# new_board_p_dan_n.net
KiCad netlist of a schematic drawn in EAGLE
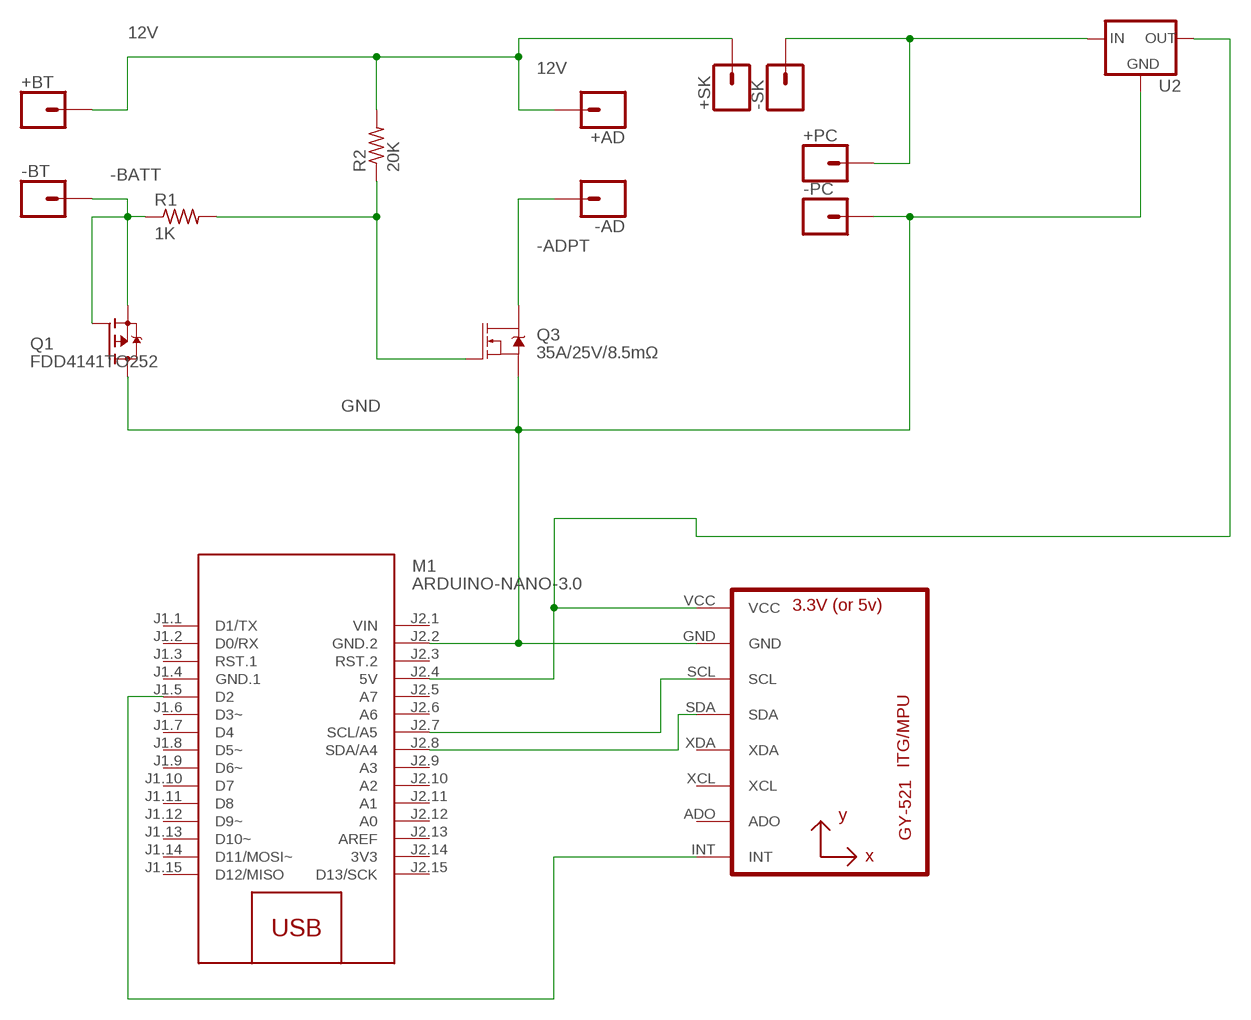
[diagram p0: schematic, sheet 1]

(export (version "E")
  (design (tool "Eeschema 10.0.6"))
  (components
    (comp (ref "+AD")
      (value "CONN_01PTH_2MM")
      (footprint "eagle-import:1X01_2MM")
      (libsource (lib "eagle-import") (part "CONN_01PTH_2MM"))
    )
    (comp (ref "+BT")
      (value "CONN_01PTH_2MM")
      (footprint "eagle-import:1X01_2MM")
      (libsource (lib "eagle-import") (part "CONN_01PTH_2MM"))
    )
    (comp (ref "+PC")
      (value "CONN_01PTH_2MM")
      (footprint "eagle-import:1X01_2MM")
      (libsource (lib "eagle-import") (part "CONN_01PTH_2MM"))
    )
    (comp (ref "+SK")
      (value "CONN_01PTH_2MM")
      (footprint "eagle-import:1X01_2MM")
      (libsource (lib "eagle-import") (part "CONN_01PTH_2MM"))
    )
    (comp (ref "-AD")
      (value "CONN_01PTH_2MM")
      (footprint "eagle-import:1X01_2MM")
      (libsource (lib "eagle-import") (part "CONN_01PTH_2MM"))
    )
    (comp (ref "-BT")
      (value "CONN_01PTH_2MM")
      (footprint "eagle-import:1X01_2MM")
      (libsource (lib "eagle-import") (part "CONN_01PTH_2MM"))
    )
    (comp (ref "-PC")
      (value "CONN_01PTH_2MM")
      (footprint "eagle-import:1X01_2MM")
      (libsource (lib "eagle-import") (part "CONN_01PTH_2MM"))
    )
    (comp (ref "-SK")
      (value "CONN_01PTH_2MM")
      (footprint "eagle-import:1X01_2MM")
      (libsource (lib "eagle-import") (part "CONN_01PTH_2MM"))
    )
    (comp (ref "M1")
      (value "ARDUINO-NANO-3.0")
      (footprint "eagle-import:ARDUINO-NANO-3.0")
      (libsource (lib "eagle-import") (part "ARDUINO-NANO-3.0"))
    )
    (comp (ref "Q1")
      (value "FDD4141TO252")
      (footprint "eagle-import:TO252")
      (libsource (lib "eagle-import") (part "FDD4141TO252"))
    )
    (comp (ref "Q3")
      (value "35A/25V/8.5mΩ")
      (footprint "eagle-import:DPAK")
      (libsource (lib "eagle-import") (part "MOSFET-NCH-FDD8780"))
    )
    (comp (ref "R1")
      (value "1K")
      (footprint "eagle-import:M1206")
      (libsource (lib "eagle-import") (part "R-US_M1206"))
    )
    (comp (ref "R2")
      (value "20K")
      (footprint "eagle-import:M1206")
      (libsource (lib "eagle-import") (part "R-US_M1206"))
    )
    (comp (ref "U1")
      (value "GY-521MPU6050")
      (footprint "eagle-import:GY-521")
      (libsource (lib "eagle-import") (part "GY-521MPU6050"))
    )
    (comp (ref "U2")
      (value "+12v")
      (footprint "eagle-import:TO-252")
      (libsource (lib "eagle-import") (part "V_REG_78XX7812"))
    )
  )
  (nets
    (net (code "1") (name "/-ADPT") (class "Default")
      (node (ref "-AD") (pin "1") (pinfunction "1_1") (pintype "passive"))
      (node (ref "Q3") (pin "4") (pinfunction "D_4") (pintype "bidirectional"))
    )
    (net (code "2") (name "/-BATT") (class "Default")
      (node (ref "-BT") (pin "1") (pinfunction "1_1") (pintype "passive"))
      (node (ref "Q1") (pin "1") (pinfunction "G_1") (pintype "passive"))
      (node (ref "Q1") (pin "2") (pinfunction "S_2") (pintype "passive"))
      (node (ref "R1") (pin "1") (pinfunction "1_1") (pintype "passive"))
    )
    (net (code "3") (name "/3V3") (class "Default")
      (node (ref "M1") (pin "J2.14") (pinfunction "3V3_J2.14") (pintype "power_in"))
    )
    (net (code "4") (name "/12V") (class "Default")
      (node (ref "+AD") (pin "1") (pinfunction "1_1") (pintype "passive"))
      (node (ref "+BT") (pin "1") (pinfunction "1_1") (pintype "passive"))
      (node (ref "+SK") (pin "1") (pinfunction "1_1") (pintype "passive"))
      (node (ref "R2") (pin "2") (pinfunction "2_2") (pintype "passive"))
    )
    (net (code "5") (name "/GND") (class "Default")
      (node (ref "-PC") (pin "1") (pinfunction "1_1") (pintype "passive"))
      (node (ref "M1") (pin "J2.2") (pinfunction "GND.2_J2.2") (pintype "power_in"))
      (node (ref "Q1") (pin "3") (pinfunction "D_3") (pintype "passive"))
      (node (ref "Q3") (pin "3") (pinfunction "S_3") (pintype "bidirectional"))
      (node (ref "U1") (pin "GND") (pinfunction "GND_GND") (pintype "bidirectional"))
      (node (ref "U2") (pin "3") (pinfunction "GND_3") (pintype "input"))
    )
    (net (code "6") (name "/GND.1") (class "Default")
      (node (ref "M1") (pin "J1.4") (pinfunction "GND.1_J1.4") (pintype "power_in"))
    )
    (net (code "7") (name "/VIN") (class "Default")
      (node (ref "M1") (pin "J2.1") (pinfunction "VIN_J2.1") (pintype "power_in"))
    )
    (net (code "8") (name "Net-(M1-5V)") (class "Default")
      (node (ref "M1") (pin "J2.4") (pinfunction "5V_J2.4") (pintype "power_in"))
      (node (ref "U1") (pin "VCC") (pinfunction "VCC_VCC") (pintype "bidirectional"))
      (node (ref "U2") (pin "2") (pinfunction "OUT_2") (pintype "passive"))
    )
    (net (code "9") (name "Net-(M1-D2)") (class "Default")
      (node (ref "M1") (pin "J1.5") (pinfunction "D2_J1.5") (pintype "bidirectional"))
      (node (ref "U1") (pin "INT") (pinfunction "INT_INT") (pintype "bidirectional"))
    )
    (net (code "10") (name "Net-(M1-SCL{slash}A5)") (class "Default")
      (node (ref "M1") (pin "J2.7") (pinfunction "SCL/A5_J2.7") (pintype "bidirectional"))
      (node (ref "U1") (pin "SCL") (pinfunction "SCL_SCL") (pintype "bidirectional"))
    )
    (net (code "11") (name "Net-(M1-SDA{slash}A4)") (class "Default")
      (node (ref "M1") (pin "J2.8") (pinfunction "SDA/A4_J2.8") (pintype "bidirectional"))
      (node (ref "U1") (pin "SDA") (pinfunction "SDA_SDA") (pintype "bidirectional"))
    )
    (net (code "12") (name "Net-(Q3-G)") (class "Default")
      (node (ref "Q3") (pin "1") (pinfunction "G_1") (pintype "bidirectional"))
      (node (ref "R1") (pin "2") (pinfunction "2_2") (pintype "passive"))
      (node (ref "R2") (pin "1") (pinfunction "1_1") (pintype "passive"))
    )
    (net (code "13") (name "Net-(U2-IN)") (class "Default")
      (node (ref "+PC") (pin "1") (pinfunction "1_1") (pintype "passive"))
      (node (ref "-SK") (pin "1") (pinfunction "1_1") (pintype "passive"))
      (node (ref "U2") (pin "1") (pinfunction "IN_1") (pintype "input"))
    )
    (net (code "14") (name "unconnected-(M1-A0-PadJ2.12)") (class "Default")
      (node (ref "M1") (pin "J2.12") (pinfunction "A0_J2.12") (pintype "bidirectional"))
    )
    (net (code "15") (name "unconnected-(M1-A1-PadJ2.11)") (class "Default")
      (node (ref "M1") (pin "J2.11") (pinfunction "A1_J2.11") (pintype "bidirectional"))
    )
    (net (code "16") (name "unconnected-(M1-A2-PadJ2.10)") (class "Default")
      (node (ref "M1") (pin "J2.10") (pinfunction "A2_J2.10") (pintype "bidirectional"))
    )
    (net (code "17") (name "unconnected-(M1-A3-PadJ2.9)") (class "Default")
      (node (ref "M1") (pin "J2.9") (pinfunction "A3_J2.9") (pintype "bidirectional"))
    )
    (net (code "18") (name "unconnected-(M1-A6-PadJ2.6)") (class "Default")
      (node (ref "M1") (pin "J2.6") (pinfunction "A6_J2.6") (pintype "bidirectional"))
    )
    (net (code "19") (name "unconnected-(M1-A7-PadJ2.5)") (class "Default")
      (node (ref "M1") (pin "J2.5") (pinfunction "A7_J2.5") (pintype "bidirectional"))
    )
    (net (code "20") (name "unconnected-(M1-AREF-PadJ2.13)") (class "Default")
      (node (ref "M1") (pin "J2.13") (pinfunction "AREF_J2.13") (pintype "bidirectional"))
    )
    (net (code "21") (name "unconnected-(M1-D0{slash}RX-PadJ1.2)") (class "Default")
      (node (ref "M1") (pin "J1.2") (pinfunction "D0/RX_J1.2") (pintype "bidirectional"))
    )
    (net (code "22") (name "unconnected-(M1-D1{slash}TX-PadJ1.1)") (class "Default")
      (node (ref "M1") (pin "J1.1") (pinfunction "D1/TX_J1.1") (pintype "bidirectional"))
    )
    (net (code "23") (name "unconnected-(M1-D3~{}-PadJ1.6)") (class "Default")
      (node (ref "M1") (pin "J1.6") (pinfunction "D3~{}_J1.6") (pintype "bidirectional"))
    )
    (net (code "24") (name "unconnected-(M1-D4-PadJ1.7)") (class "Default")
      (node (ref "M1") (pin "J1.7") (pinfunction "D4_J1.7") (pintype "bidirectional"))
    )
    (net (code "25") (name "unconnected-(M1-D5~{}-PadJ1.8)") (class "Default")
      (node (ref "M1") (pin "J1.8") (pinfunction "D5~{}_J1.8") (pintype "bidirectional"))
    )
    (net (code "26") (name "unconnected-(M1-D6~{}-PadJ1.9)") (class "Default")
      (node (ref "M1") (pin "J1.9") (pinfunction "D6~{}_J1.9") (pintype "bidirectional"))
    )
    (net (code "27") (name "unconnected-(M1-D7-PadJ1.10)") (class "Default")
      (node (ref "M1") (pin "J1.10") (pinfunction "D7_J1.10") (pintype "bidirectional"))
    )
    (net (code "28") (name "unconnected-(M1-D8-PadJ1.11)") (class "Default")
      (node (ref "M1") (pin "J1.11") (pinfunction "D8_J1.11") (pintype "bidirectional"))
    )
    (net (code "29") (name "unconnected-(M1-D9~{}-PadJ1.12)") (class "Default")
      (node (ref "M1") (pin "J1.12") (pinfunction "D9~{}_J1.12") (pintype "bidirectional"))
    )
    (net (code "30") (name "unconnected-(M1-D10~{}-PadJ1.13)") (class "Default")
      (node (ref "M1") (pin "J1.13") (pinfunction "D10~{}_J1.13") (pintype "bidirectional"))
    )
    (net (code "31") (name "unconnected-(M1-D11{slash}MOSI~{}-PadJ1.14)") (class "Default")
      (node (ref "M1") (pin "J1.14") (pinfunction "D11/MOSI~{}_J1.14") (pintype "bidirectional"))
    )
    (net (code "32") (name "unconnected-(M1-D12{slash}MISO-PadJ1.15)") (class "Default")
      (node (ref "M1") (pin "J1.15") (pinfunction "D12/MISO_J1.15") (pintype "bidirectional"))
    )
    (net (code "33") (name "unconnected-(M1-D13{slash}SCK-PadJ2.15)") (class "Default")
      (node (ref "M1") (pin "J2.15") (pinfunction "D13/SCK_J2.15") (pintype "bidirectional"))
    )
    (net (code "34") (name "unconnected-(M1-RST.1-PadJ1.3)") (class "Default")
      (node (ref "M1") (pin "J1.3") (pinfunction "RST.1_J1.3") (pintype "bidirectional"))
    )
    (net (code "35") (name "unconnected-(M1-RST.2-PadJ2.3)") (class "Default")
      (node (ref "M1") (pin "J2.3") (pinfunction "RST.2_J2.3") (pintype "bidirectional"))
    )
    (net (code "36") (name "unconnected-(U1-PadADO)") (class "Default")
      (node (ref "U1") (pin "ADO") (pinfunction "ADO_ADO") (pintype "bidirectional"))
    )
    (net (code "37") (name "unconnected-(U1-PadXCL)") (class "Default")
      (node (ref "U1") (pin "XCL") (pinfunction "XCL_XCL") (pintype "bidirectional"))
    )
    (net (code "38") (name "unconnected-(U1-PadXDA)") (class "Default")
      (node (ref "U1") (pin "XDA") (pinfunction "XDA_XDA") (pintype "bidirectional"))
    )
  )
)
